# bbwmixer.net
KiCad netlist of a schematic drawn in EAGLE
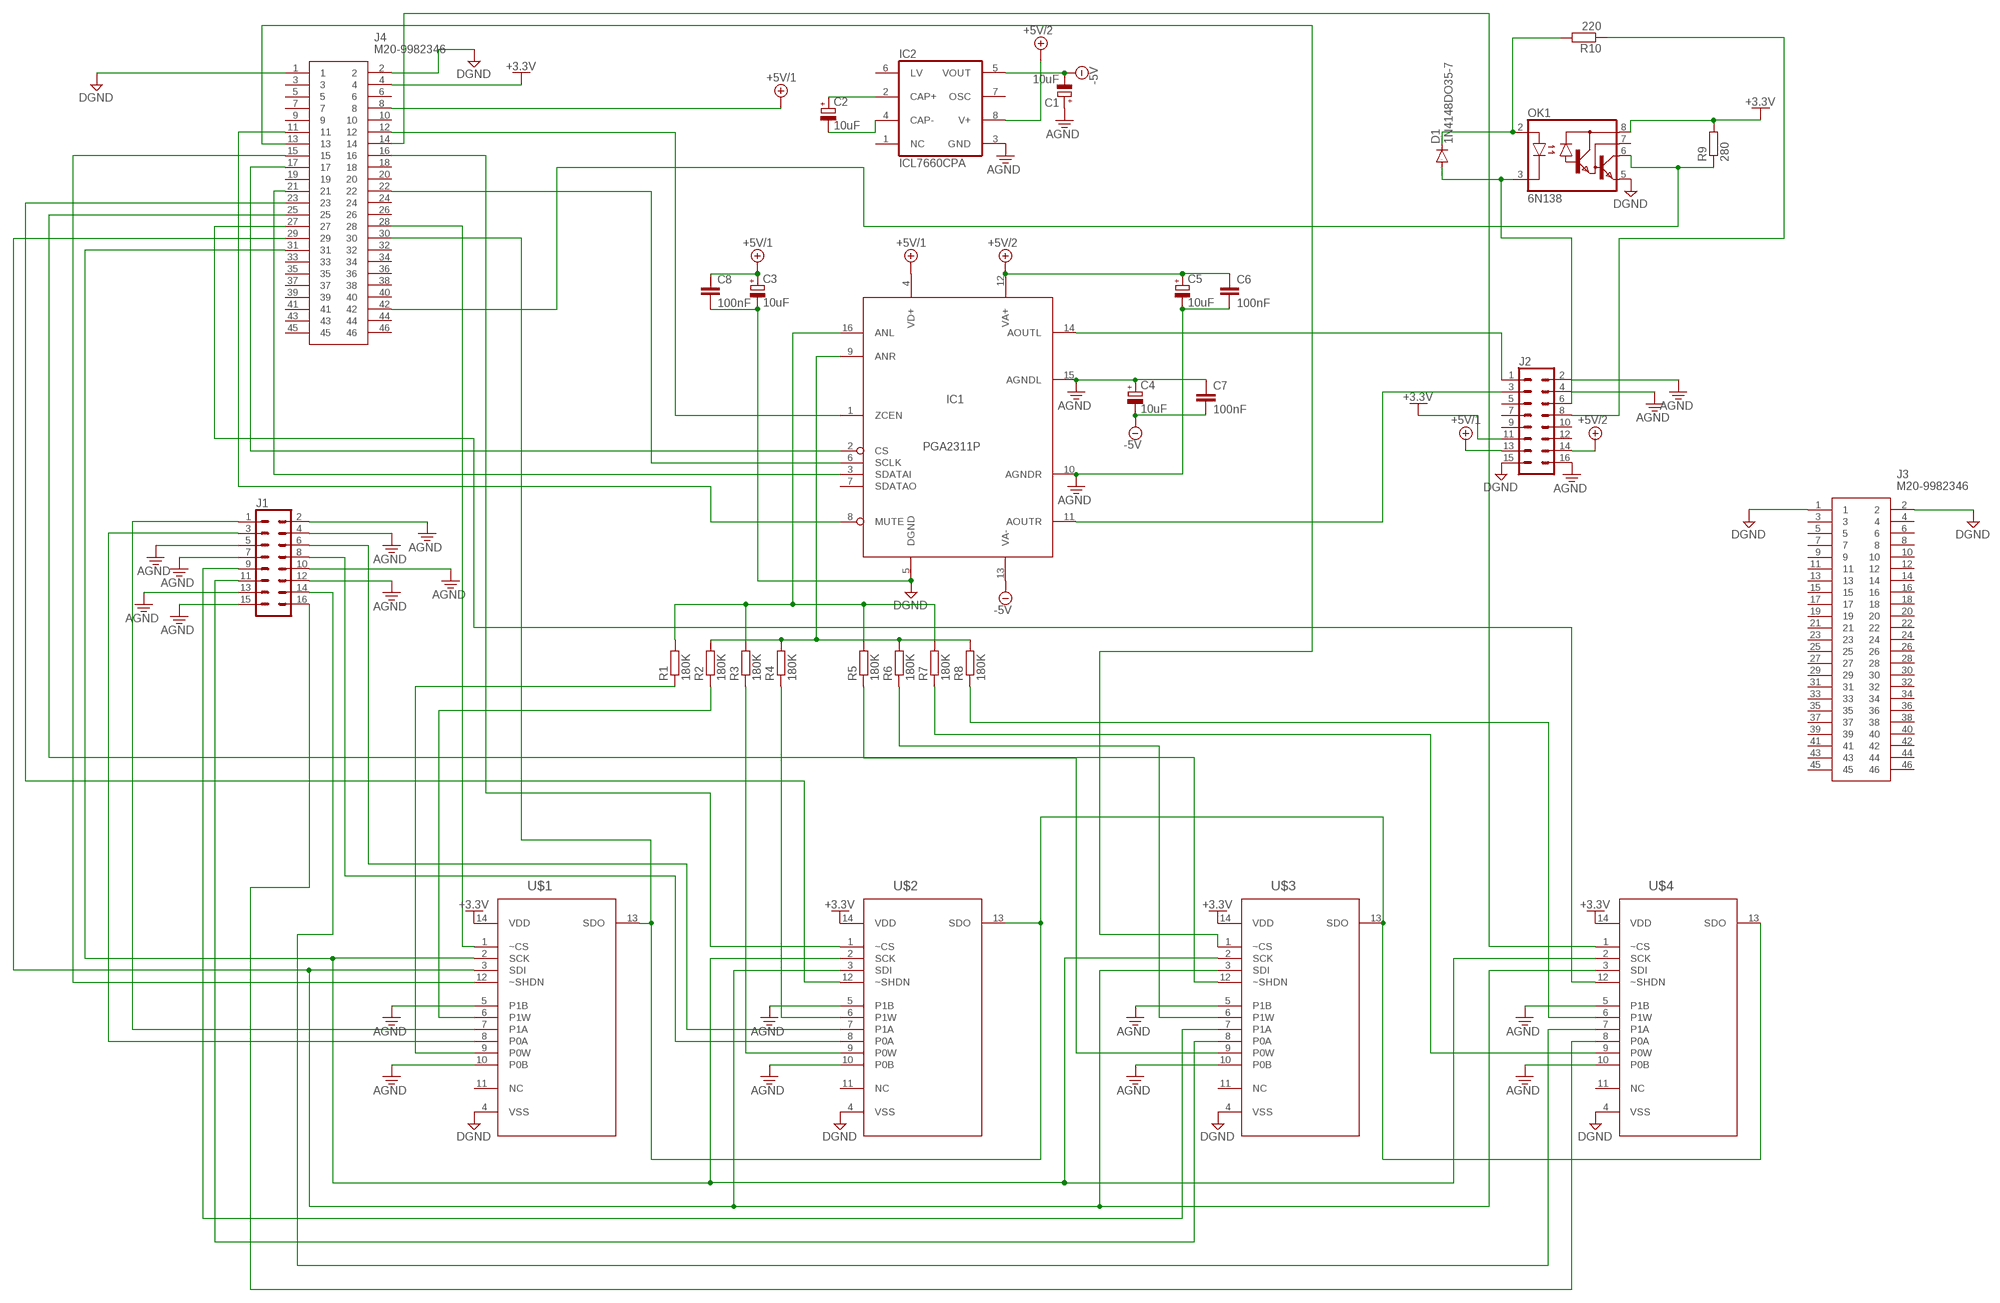
[diagram p0: schematic, sheet 1]

(export (version "E")
  (design (tool "Eeschema 10.0.6"))
  (components
    (comp (ref "C1")
      (value "10uF")
      (footprint "eagle-import:E15-5")
      (libsource (lib "eagle-import") (part "CPOL-EUE15-5AXIAL"))
    )
    (comp (ref "C2")
      (value "10uF")
      (footprint "eagle-import:E15-5")
      (libsource (lib "eagle-import") (part "CPOL-EUE15-5AXIAL"))
    )
    (comp (ref "C3")
      (value "10uF")
      (footprint "eagle-import:E15-5")
      (libsource (lib "eagle-import") (part "CPOL-EUE15-5AXIAL"))
    )
    (comp (ref "C4")
      (value "10uF")
      (footprint "eagle-import:E15-5")
      (libsource (lib "eagle-import") (part "CPOL-EUE15-5AXIAL"))
    )
    (comp (ref "C5")
      (value "10uF")
      (footprint "eagle-import:E15-5")
      (libsource (lib "eagle-import") (part "CPOL-EUE15-5AXIAL"))
    )
    (comp (ref "C6")
      (value "100nF")
      (footprint "eagle-import:C050-025X075")
      (libsource (lib "eagle-import") (part "C-EU050-025X075"))
    )
    (comp (ref "C7")
      (value "100nF")
      (footprint "eagle-import:C050-025X075")
      (libsource (lib "eagle-import") (part "C-EU050-025X075"))
    )
    (comp (ref "C8")
      (value "100nF")
      (footprint "eagle-import:C050-025X075")
      (libsource (lib "eagle-import") (part "C-EU050-025X075"))
    )
    (comp (ref "D1")
      (value "1N4148DO35-7")
      (footprint "eagle-import:DO35-7")
      (libsource (lib "eagle-import") (part "1N4148DO35-7"))
    )
    (comp (ref "IC1")
      (value "PGA2311P")
      (footprint "eagle-import:DIL16")
      (libsource (lib "eagle-import") (part "PGA2311P"))
    )
    (comp (ref "IC2")
      (value "ICL7660CPA")
      (footprint "eagle-import:DIL08")
      (fields (field (name "MF") "INTERSIL"))
      (libsource (lib "eagle-import") (part "ICL7660CPA"))
    )
    (comp (ref "J1")
      (value "CONN_08X2")
      (footprint "eagle-import:2X8")
      (libsource (lib "eagle-import") (part "CONN_08X2"))
    )
    (comp (ref "J2")
      (value "CONN_08X2")
      (footprint "eagle-import:2X8")
      (libsource (lib "eagle-import") (part "CONN_08X2"))
    )
    (comp (ref "J3")
      (value "M20-9982346")
      (footprint "eagle-import:M20-9982346")
      (fields (field (name "MOUSER_PART_NUMBER") "855-M20-9982346"))
      (libsource (lib "eagle-import") (part "M20-9982346"))
    )
    (comp (ref "J4")
      (value "M20-9982346")
      (footprint "eagle-import:M20-9982346")
      (fields (field (name "MOUSER_PART_NUMBER") "855-M20-9982346"))
      (libsource (lib "eagle-import") (part "M20-9982346"))
    )
    (comp (ref "OK1")
      (value "6N138")
      (footprint "eagle-import:DIL08")
      (fields (field (name "MF") "VISHAY/TELEFUNKEN"))
      (libsource (lib "eagle-import") (part "6N138"))
    )
    (comp (ref "R1")
      (value "180K")
      (footprint "eagle-import:0207_10")
      (libsource (lib "eagle-import") (part "R-EU_0207/10"))
    )
    (comp (ref "R2")
      (value "180K")
      (footprint "eagle-import:0207_10")
      (libsource (lib "eagle-import") (part "R-EU_0207/10"))
    )
    (comp (ref "R3")
      (value "180K")
      (footprint "eagle-import:0207_10")
      (libsource (lib "eagle-import") (part "R-EU_0207/10"))
    )
    (comp (ref "R4")
      (value "180K")
      (footprint "eagle-import:0207_10")
      (libsource (lib "eagle-import") (part "R-EU_0207/10"))
    )
    (comp (ref "R5")
      (value "180K")
      (footprint "eagle-import:0207_10")
      (libsource (lib "eagle-import") (part "R-EU_0207/10"))
    )
    (comp (ref "R6")
      (value "180K")
      (footprint "eagle-import:0207_10")
      (libsource (lib "eagle-import") (part "R-EU_0207/10"))
    )
    (comp (ref "R7")
      (value "180K")
      (footprint "eagle-import:0207_10")
      (libsource (lib "eagle-import") (part "R-EU_0207/10"))
    )
    (comp (ref "R8")
      (value "180K")
      (footprint "eagle-import:0207_10")
      (libsource (lib "eagle-import") (part "R-EU_0207/10"))
    )
    (comp (ref "R9")
      (value "280")
      (footprint "eagle-import:0207_10")
      (libsource (lib "eagle-import") (part "R-EU_0207/10"))
    )
    (comp (ref "R10")
      (value "220")
      (footprint "eagle-import:0207_10")
      (libsource (lib "eagle-import") (part "R-EU_0207/10"))
    )
    (comp (ref "U$1")
      (value "MCP4251-103E/P")
      (footprint "eagle-import:DIP254P762X533-14")
      (fields (field (name "MF") "Microchip Technology / Atmel"))
      (libsource (lib "eagle-import") (part "MCP4251-103E/P"))
    )
    (comp (ref "U$2")
      (value "MCP4251-103E/P")
      (footprint "eagle-import:DIP254P762X533-14")
      (fields (field (name "MF") "Microchip Technology / Atmel"))
      (libsource (lib "eagle-import") (part "MCP4251-103E/P"))
    )
    (comp (ref "U$3")
      (value "MCP4251-103E/P")
      (footprint "eagle-import:DIP254P762X533-14")
      (fields (field (name "MF") "Microchip Technology / Atmel"))
      (libsource (lib "eagle-import") (part "MCP4251-103E/P"))
    )
    (comp (ref "U$4")
      (value "MCP4251-103E/P")
      (footprint "eagle-import:DIP254P762X533-14")
      (fields (field (name "MF") "Microchip Technology / Atmel"))
      (libsource (lib "eagle-import") (part "MCP4251-103E/P"))
    )
  )
  (nets
    (net (code "1") (name "+3.3V") (class "Default")
      (node (ref "J2") (pin "11") (pinfunction "11_11") (pintype "passive"))
      (node (ref "J4") (pin "4") (pinfunction "4_4") (pintype "bidirectional"))
      (node (ref "OK1") (pin "8") (pinfunction "VCC_8") (pintype "passive"))
      (node (ref "R9") (pin "2") (pinfunction "2_2") (pintype "passive"))
      (node (ref "U$1") (pin "14") (pinfunction "VDD_14") (pintype "power_in"))
      (node (ref "U$2") (pin "14") (pinfunction "VDD_14") (pintype "power_in"))
      (node (ref "U$3") (pin "14") (pinfunction "VDD_14") (pintype "power_in"))
      (node (ref "U$4") (pin "14") (pinfunction "VDD_14") (pintype "power_in"))
    )
    (net (code "2") (name "+5V{slash}1") (class "Default")
      (node (ref "C3") (pin "+") (pinfunction "+_+") (pintype "passive"))
      (node (ref "C8") (pin "1") (pinfunction "1_1") (pintype "passive"))
      (node (ref "IC1") (pin "4") (pinfunction "VD+_4") (pintype "power_in"))
      (node (ref "J2") (pin "13") (pinfunction "13_13") (pintype "passive"))
      (node (ref "J4") (pin "8") (pinfunction "8_8") (pintype "bidirectional"))
    )
    (net (code "3") (name "+5V{slash}2") (class "Default")
      (node (ref "IC1") (pin "12") (pinfunction "VA+_12") (pintype "power_in"))
      (node (ref "IC2") (pin "8") (pinfunction "V+_8") (pintype "power_in"))
      (node (ref "J2") (pin "14") (pinfunction "14_14") (pintype "passive"))
    )
    (net (code "4") (name "-5V") (class "Default")
      (node (ref "C1") (pin "-") (pinfunction "-_-") (pintype "passive"))
      (node (ref "C4") (pin "-") (pinfunction "-_-") (pintype "passive"))
      (node (ref "C7") (pin "2") (pinfunction "2_2") (pintype "passive"))
      (node (ref "IC1") (pin "13") (pinfunction "VA-_13") (pintype "power_in"))
      (node (ref "IC2") (pin "5") (pinfunction "VOUT_5") (pintype "output"))
    )
    (net (code "5") (name "AGND") (class "Default")
      (node (ref "C1") (pin "+") (pinfunction "+_+") (pintype "passive"))
      (node (ref "C4") (pin "+") (pinfunction "+_+") (pintype "passive"))
      (node (ref "C5") (pin "-") (pinfunction "-_-") (pintype "passive"))
      (node (ref "C6") (pin "2") (pinfunction "2_2") (pintype "passive"))
      (node (ref "C7") (pin "1") (pinfunction "1_1") (pintype "passive"))
      (node (ref "IC1") (pin "10") (pinfunction "AGNDR_10") (pintype "power_in"))
      (node (ref "IC1") (pin "15") (pinfunction "AGNDL_15") (pintype "power_in"))
      (node (ref "IC2") (pin "3") (pinfunction "GND_3") (pintype "power_in"))
      (node (ref "J1") (pin "10") (pinfunction "10_10") (pintype "passive"))
      (node (ref "J1") (pin "12") (pinfunction "12_12") (pintype "passive"))
      (node (ref "J1") (pin "13") (pinfunction "13_13") (pintype "passive"))
      (node (ref "J1") (pin "15") (pinfunction "15_15") (pintype "passive"))
      (node (ref "J1") (pin "2") (pinfunction "2_2") (pintype "passive"))
      (node (ref "J1") (pin "4") (pinfunction "4_4") (pintype "passive"))
      (node (ref "J1") (pin "5") (pinfunction "5_5") (pintype "passive"))
      (node (ref "J1") (pin "7") (pinfunction "7_7") (pintype "passive"))
      (node (ref "J2") (pin "16") (pinfunction "16_16") (pintype "passive"))
      (node (ref "J2") (pin "2") (pinfunction "2_2") (pintype "passive"))
      (node (ref "J2") (pin "4") (pinfunction "4_4") (pintype "passive"))
      (node (ref "U$1") (pin "10") (pinfunction "P0B_10") (pintype "passive"))
      (node (ref "U$1") (pin "5") (pinfunction "P1B_5") (pintype "passive"))
      (node (ref "U$2") (pin "10") (pinfunction "P0B_10") (pintype "passive"))
      (node (ref "U$2") (pin "5") (pinfunction "P1B_5") (pintype "passive"))
      (node (ref "U$3") (pin "10") (pinfunction "P0B_10") (pintype "passive"))
      (node (ref "U$3") (pin "5") (pinfunction "P1B_5") (pintype "passive"))
      (node (ref "U$4") (pin "10") (pinfunction "P0B_10") (pintype "passive"))
      (node (ref "U$4") (pin "5") (pinfunction "P1B_5") (pintype "passive"))
    )
    (net (code "6") (name "DGND") (class "Default")
      (node (ref "C3") (pin "-") (pinfunction "-_-") (pintype "passive"))
      (node (ref "C8") (pin "2") (pinfunction "2_2") (pintype "passive"))
      (node (ref "IC1") (pin "5") (pinfunction "DGND_5") (pintype "power_in"))
      (node (ref "J2") (pin "15") (pinfunction "15_15") (pintype "passive"))
      (node (ref "J3") (pin "1") (pinfunction "1_1") (pintype "bidirectional"))
      (node (ref "J3") (pin "2") (pinfunction "2_2") (pintype "bidirectional"))
      (node (ref "J4") (pin "1") (pinfunction "1_1") (pintype "bidirectional"))
      (node (ref "J4") (pin "2") (pinfunction "2_2") (pintype "bidirectional"))
      (node (ref "OK1") (pin "5") (pinfunction "GND_5") (pintype "passive"))
      (node (ref "U$1") (pin "4") (pinfunction "VSS_4") (pintype "passive"))
      (node (ref "U$2") (pin "4") (pinfunction "VSS_4") (pintype "passive"))
      (node (ref "U$3") (pin "4") (pinfunction "VSS_4") (pintype "passive"))
      (node (ref "U$4") (pin "4") (pinfunction "VSS_4") (pintype "passive"))
    )
    (net (code "7") (name "Net-(C5-Pad+)") (class "Default")
      (node (ref "C5") (pin "+") (pinfunction "+_+") (pintype "passive"))
      (node (ref "C6") (pin "1") (pinfunction "1_1") (pintype "passive"))
    )
    (net (code "8") (name "Net-(IC1-ANL)") (class "Default")
      (node (ref "IC1") (pin "16") (pinfunction "ANL_16") (pintype "input"))
      (node (ref "R1") (pin "2") (pinfunction "2_2") (pintype "passive"))
      (node (ref "R3") (pin "2") (pinfunction "2_2") (pintype "passive"))
      (node (ref "R5") (pin "2") (pinfunction "2_2") (pintype "passive"))
      (node (ref "R7") (pin "2") (pinfunction "2_2") (pintype "passive"))
    )
    (net (code "9") (name "Net-(IC1-ANR)") (class "Default")
      (node (ref "IC1") (pin "9") (pinfunction "ANR_9") (pintype "input"))
      (node (ref "R2") (pin "2") (pinfunction "2_2") (pintype "passive"))
      (node (ref "R4") (pin "2") (pinfunction "2_2") (pintype "passive"))
      (node (ref "R6") (pin "2") (pinfunction "2_2") (pintype "passive"))
      (node (ref "R8") (pin "2") (pinfunction "2_2") (pintype "passive"))
    )
    (net (code "10") (name "Net-(IC1-AOUTL)") (class "Default")
      (node (ref "IC1") (pin "14") (pinfunction "AOUTL_14") (pintype "output"))
      (node (ref "J2") (pin "1") (pinfunction "1_1") (pintype "passive"))
    )
    (net (code "11") (name "Net-(IC1-AOUTR)") (class "Default")
      (node (ref "IC1") (pin "11") (pinfunction "AOUTR_11") (pintype "output"))
      (node (ref "J2") (pin "3") (pinfunction "3_3") (pintype "passive"))
    )
    (net (code "12") (name "Net-(IC1-CS)") (class "Default")
      (node (ref "IC1") (pin "2") (pinfunction "CS_2") (pintype "input"))
      (node (ref "J4") (pin "17") (pinfunction "17_17") (pintype "bidirectional"))
    )
    (net (code "13") (name "Net-(IC1-MUTE)") (class "Default")
      (node (ref "IC1") (pin "8") (pinfunction "MUTE_8") (pintype "input"))
      (node (ref "J4") (pin "11") (pinfunction "11_11") (pintype "bidirectional"))
    )
    (net (code "14") (name "Net-(IC1-SCLK)") (class "Default")
      (node (ref "IC1") (pin "6") (pinfunction "SCLK_6") (pintype "input"))
      (node (ref "J4") (pin "22") (pinfunction "22_22") (pintype "bidirectional"))
    )
    (net (code "15") (name "Net-(IC1-SDATAI)") (class "Default")
      (node (ref "IC1") (pin "3") (pinfunction "SDATAI_3") (pintype "input"))
      (node (ref "J4") (pin "21") (pinfunction "21_21") (pintype "bidirectional"))
    )
    (net (code "16") (name "Net-(IC1-ZCEN)") (class "Default")
      (node (ref "IC1") (pin "1") (pinfunction "ZCEN_1") (pintype "input"))
      (node (ref "J4") (pin "12") (pinfunction "12_12") (pintype "bidirectional"))
    )
    (net (code "17") (name "Net-(IC2-CAP+)") (class "Default")
      (node (ref "C2") (pin "+") (pinfunction "+_+") (pintype "passive"))
      (node (ref "IC2") (pin "2") (pinfunction "CAP+_2") (pintype "passive"))
    )
    (net (code "18") (name "Net-(IC2-CAP-)") (class "Default")
      (node (ref "C2") (pin "-") (pinfunction "-_-") (pintype "passive"))
      (node (ref "IC2") (pin "4") (pinfunction "CAP-_4") (pintype "passive"))
    )
    (net (code "19") (name "Net-(J2-Pad8)") (class "Default")
      (node (ref "J2") (pin "8") (pinfunction "8_8") (pintype "passive"))
      (node (ref "R10") (pin "1") (pinfunction "1_1") (pintype "passive"))
    )
    (net (code "20") (name "Net-(OK1-A)") (class "Default")
      (node (ref "D1") (pin "C") (pinfunction "C_C") (pintype "passive"))
      (node (ref "OK1") (pin "2") (pinfunction "A_2") (pintype "passive"))
      (node (ref "R10") (pin "2") (pinfunction "2_2") (pintype "passive"))
    )
    (net (code "21") (name "Net-(OK1-C)") (class "Default")
      (node (ref "D1") (pin "A") (pinfunction "A_A") (pintype "passive"))
      (node (ref "J2") (pin "6") (pinfunction "6_6") (pintype "passive"))
      (node (ref "OK1") (pin "3") (pinfunction "C_3") (pintype "passive"))
    )
    (net (code "22") (name "Net-(OK1-VO)") (class "Default")
      (node (ref "J4") (pin "42") (pinfunction "42_42") (pintype "bidirectional"))
      (node (ref "OK1") (pin "6") (pinfunction "VO_6") (pintype "passive"))
      (node (ref "R9") (pin "1") (pinfunction "1_1") (pintype "passive"))
    )
    (net (code "23") (name "Net-(U$1-P0A)") (class "Default")
      (node (ref "J1") (pin "3") (pinfunction "3_3") (pintype "passive"))
      (node (ref "U$1") (pin "8") (pinfunction "P0A_8") (pintype "passive"))
    )
    (net (code "24") (name "Net-(U$1-P0W)") (class "Default")
      (node (ref "R1") (pin "1") (pinfunction "1_1") (pintype "passive"))
      (node (ref "U$1") (pin "9") (pinfunction "P0W_9") (pintype "passive"))
    )
    (net (code "25") (name "Net-(U$1-P1A)") (class "Default")
      (node (ref "J1") (pin "1") (pinfunction "1_1") (pintype "passive"))
      (node (ref "U$1") (pin "7") (pinfunction "P1A_7") (pintype "passive"))
    )
    (net (code "26") (name "Net-(U$1-P1W)") (class "Default")
      (node (ref "R2") (pin "1") (pinfunction "1_1") (pintype "passive"))
      (node (ref "U$1") (pin "6") (pinfunction "P1W_6") (pintype "passive"))
    )
    (net (code "27") (name "Net-(U$1-SCK)") (class "Default")
      (node (ref "J4") (pin "31") (pinfunction "31_31") (pintype "bidirectional"))
      (node (ref "U$1") (pin "2") (pinfunction "SCK_2") (pintype "input"))
      (node (ref "U$2") (pin "2") (pinfunction "SCK_2") (pintype "input"))
      (node (ref "U$3") (pin "2") (pinfunction "SCK_2") (pintype "input"))
      (node (ref "U$4") (pin "2") (pinfunction "SCK_2") (pintype "input"))
    )
    (net (code "28") (name "Net-(U$1-SDI)") (class "Default")
      (node (ref "J4") (pin "29") (pinfunction "29_29") (pintype "bidirectional"))
      (node (ref "U$1") (pin "3") (pinfunction "SDI_3") (pintype "input"))
      (node (ref "U$2") (pin "3") (pinfunction "SDI_3") (pintype "input"))
      (node (ref "U$3") (pin "3") (pinfunction "SDI_3") (pintype "input"))
      (node (ref "U$4") (pin "3") (pinfunction "SDI_3") (pintype "input"))
    )
    (net (code "29") (name "Net-(U$1-SDO)") (class "Default")
      (node (ref "J4") (pin "30") (pinfunction "30_30") (pintype "bidirectional"))
      (node (ref "U$1") (pin "13") (pinfunction "SDO_13") (pintype "output"))
      (node (ref "U$2") (pin "13") (pinfunction "SDO_13") (pintype "output"))
      (node (ref "U$3") (pin "13") (pinfunction "SDO_13") (pintype "output"))
      (node (ref "U$4") (pin "13") (pinfunction "SDO_13") (pintype "output"))
    )
    (net (code "30") (name "Net-(U$1-~{CS})") (class "Default")
      (node (ref "J4") (pin "28") (pinfunction "28_28") (pintype "bidirectional"))
      (node (ref "U$1") (pin "1") (pinfunction "~{CS}_1") (pintype "input"))
    )
    (net (code "31") (name "Net-(U$1-~{SHDN})") (class "Default")
      (node (ref "J4") (pin "15") (pinfunction "15_15") (pintype "bidirectional"))
      (node (ref "U$1") (pin "12") (pinfunction "~{SHDN}_12") (pintype "input"))
    )
    (net (code "32") (name "Net-(U$2-P0A)") (class "Default")
      (node (ref "J1") (pin "8") (pinfunction "8_8") (pintype "passive"))
      (node (ref "U$2") (pin "8") (pinfunction "P0A_8") (pintype "passive"))
    )
    (net (code "33") (name "Net-(U$2-P0W)") (class "Default")
      (node (ref "R3") (pin "1") (pinfunction "1_1") (pintype "passive"))
      (node (ref "U$2") (pin "9") (pinfunction "P0W_9") (pintype "passive"))
    )
    (net (code "34") (name "Net-(U$2-P1A)") (class "Default")
      (node (ref "J1") (pin "6") (pinfunction "6_6") (pintype "passive"))
      (node (ref "U$2") (pin "7") (pinfunction "P1A_7") (pintype "passive"))
    )
    (net (code "35") (name "Net-(U$2-P1W)") (class "Default")
      (node (ref "R4") (pin "1") (pinfunction "1_1") (pintype "passive"))
      (node (ref "U$2") (pin "6") (pinfunction "P1W_6") (pintype "passive"))
    )
    (net (code "36") (name "Net-(U$2-~{CS})") (class "Default")
      (node (ref "J4") (pin "16") (pinfunction "16_16") (pintype "bidirectional"))
      (node (ref "U$2") (pin "1") (pinfunction "~{CS}_1") (pintype "input"))
    )
    (net (code "37") (name "Net-(U$2-~{SHDN})") (class "Default")
      (node (ref "J4") (pin "23") (pinfunction "23_23") (pintype "bidirectional"))
      (node (ref "U$2") (pin "12") (pinfunction "~{SHDN}_12") (pintype "input"))
    )
    (net (code "38") (name "Net-(U$3-P0A)") (class "Default")
      (node (ref "J1") (pin "11") (pinfunction "11_11") (pintype "passive"))
      (node (ref "U$3") (pin "8") (pinfunction "P0A_8") (pintype "passive"))
    )
    (net (code "39") (name "Net-(U$3-P0W)") (class "Default")
      (node (ref "R5") (pin "1") (pinfunction "1_1") (pintype "passive"))
      (node (ref "U$3") (pin "9") (pinfunction "P0W_9") (pintype "passive"))
    )
    (net (code "40") (name "Net-(U$3-P1A)") (class "Default")
      (node (ref "J1") (pin "9") (pinfunction "9_9") (pintype "passive"))
      (node (ref "U$3") (pin "7") (pinfunction "P1A_7") (pintype "passive"))
    )
    (net (code "41") (name "Net-(U$3-P1W)") (class "Default")
      (node (ref "R6") (pin "1") (pinfunction "1_1") (pintype "passive"))
      (node (ref "U$3") (pin "6") (pinfunction "P1W_6") (pintype "passive"))
    )
    (net (code "42") (name "Net-(U$3-~{CS})") (class "Default")
      (node (ref "J4") (pin "13") (pinfunction "13_13") (pintype "bidirectional"))
      (node (ref "U$3") (pin "1") (pinfunction "~{CS}_1") (pintype "input"))
    )
    (net (code "43") (name "Net-(U$3-~{SHDN})") (class "Default")
      (node (ref "J4") (pin "25") (pinfunction "25_25") (pintype "bidirectional"))
      (node (ref "U$3") (pin "12") (pinfunction "~{SHDN}_12") (pintype "input"))
    )
    (net (code "44") (name "Net-(U$4-P0A)") (class "Default")
      (node (ref "J1") (pin "16") (pinfunction "16_16") (pintype "passive"))
      (node (ref "U$4") (pin "8") (pinfunction "P0A_8") (pintype "passive"))
    )
    (net (code "45") (name "Net-(U$4-P0W)") (class "Default")
      (node (ref "R7") (pin "1") (pinfunction "1_1") (pintype "passive"))
      (node (ref "U$4") (pin "9") (pinfunction "P0W_9") (pintype "passive"))
    )
    (net (code "46") (name "Net-(U$4-P1A)") (class "Default")
      (node (ref "J1") (pin "14") (pinfunction "14_14") (pintype "passive"))
      (node (ref "U$4") (pin "7") (pinfunction "P1A_7") (pintype "passive"))
    )
    (net (code "47") (name "Net-(U$4-P1W)") (class "Default")
      (node (ref "R8") (pin "1") (pinfunction "1_1") (pintype "passive"))
      (node (ref "U$4") (pin "6") (pinfunction "P1W_6") (pintype "passive"))
    )
    (net (code "48") (name "Net-(U$4-~{CS})") (class "Default")
      (node (ref "J4") (pin "14") (pinfunction "14_14") (pintype "bidirectional"))
      (node (ref "U$4") (pin "1") (pinfunction "~{CS}_1") (pintype "input"))
    )
    (net (code "49") (name "Net-(U$4-~{SHDN})") (class "Default")
      (node (ref "J4") (pin "27") (pinfunction "27_27") (pintype "bidirectional"))
      (node (ref "U$4") (pin "12") (pinfunction "~{SHDN}_12") (pintype "input"))
    )
    (net (code "50") (name "unconnected-(IC1-SDATAO-Pad7)") (class "Default")
      (node (ref "IC1") (pin "7") (pinfunction "SDATAO_7") (pintype "output"))
    )
    (net (code "51") (name "unconnected-(IC2-LV-Pad6)") (class "Default")
      (node (ref "IC2") (pin "6") (pinfunction "LV_6") (pintype "passive"))
    )
    (net (code "52") (name "unconnected-(IC2-NC-Pad1)") (class "Default")
      (node (ref "IC2") (pin "1") (pinfunction "NC_1") (pintype "no_connect"))
    )
    (net (code "53") (name "unconnected-(IC2-OSC-Pad7)") (class "Default")
      (node (ref "IC2") (pin "7") (pinfunction "OSC_7") (pintype "output"))
    )
    (net (code "54") (name "unconnected-(J2-Pad5)") (class "Default")
      (node (ref "J2") (pin "5") (pinfunction "5_5") (pintype "passive"))
    )
    (net (code "55") (name "unconnected-(J2-Pad7)") (class "Default")
      (node (ref "J2") (pin "7") (pinfunction "7_7") (pintype "passive"))
    )
    (net (code "56") (name "unconnected-(J2-Pad9)") (class "Default")
      (node (ref "J2") (pin "9") (pinfunction "9_9") (pintype "passive"))
    )
    (net (code "57") (name "unconnected-(J2-Pad10)") (class "Default")
      (node (ref "J2") (pin "10") (pinfunction "10_10") (pintype "passive"))
    )
    (net (code "58") (name "unconnected-(J2-Pad12)") (class "Default")
      (node (ref "J2") (pin "12") (pinfunction "12_12") (pintype "passive"))
    )
    (net (code "59") (name "unconnected-(J3-Pad3)") (class "Default")
      (node (ref "J3") (pin "3") (pinfunction "3_3") (pintype "bidirectional"))
    )
    (net (code "60") (name "unconnected-(J3-Pad4)") (class "Default")
      (node (ref "J3") (pin "4") (pinfunction "4_4") (pintype "bidirectional"))
    )
    (net (code "61") (name "unconnected-(J3-Pad5)") (class "Default")
      (node (ref "J3") (pin "5") (pinfunction "5_5") (pintype "bidirectional"))
    )
    (net (code "62") (name "unconnected-(J3-Pad6)") (class "Default")
      (node (ref "J3") (pin "6") (pinfunction "6_6") (pintype "bidirectional"))
    )
    (net (code "63") (name "unconnected-(J3-Pad7)") (class "Default")
      (node (ref "J3") (pin "7") (pinfunction "7_7") (pintype "bidirectional"))
    )
    (net (code "64") (name "unconnected-(J3-Pad8)") (class "Default")
      (node (ref "J3") (pin "8") (pinfunction "8_8") (pintype "bidirectional"))
    )
    (net (code "65") (name "unconnected-(J3-Pad9)") (class "Default")
      (node (ref "J3") (pin "9") (pinfunction "9_9") (pintype "bidirectional"))
    )
    (net (code "66") (name "unconnected-(J3-Pad10)") (class "Default")
      (node (ref "J3") (pin "10") (pinfunction "10_10") (pintype "bidirectional"))
    )
    (net (code "67") (name "unconnected-(J3-Pad11)") (class "Default")
      (node (ref "J3") (pin "11") (pinfunction "11_11") (pintype "bidirectional"))
    )
    (net (code "68") (name "unconnected-(J3-Pad12)") (class "Default")
      (node (ref "J3") (pin "12") (pinfunction "12_12") (pintype "bidirectional"))
    )
    (net (code "69") (name "unconnected-(J3-Pad13)") (class "Default")
      (node (ref "J3") (pin "13") (pinfunction "13_13") (pintype "bidirectional"))
    )
    (net (code "70") (name "unconnected-(J3-Pad14)") (class "Default")
      (node (ref "J3") (pin "14") (pinfunction "14_14") (pintype "bidirectional"))
    )
    (net (code "71") (name "unconnected-(J3-Pad15)") (class "Default")
      (node (ref "J3") (pin "15") (pinfunction "15_15") (pintype "bidirectional"))
    )
    (net (code "72") (name "unconnected-(J3-Pad16)") (class "Default")
      (node (ref "J3") (pin "16") (pinfunction "16_16") (pintype "bidirectional"))
    )
    (net (code "73") (name "unconnected-(J3-Pad17)") (class "Default")
      (node (ref "J3") (pin "17") (pinfunction "17_17") (pintype "bidirectional"))
    )
    (net (code "74") (name "unconnected-(J3-Pad18)") (class "Default")
      (node (ref "J3") (pin "18") (pinfunction "18_18") (pintype "bidirectional"))
    )
    (net (code "75") (name "unconnected-(J3-Pad19)") (class "Default")
      (node (ref "J3") (pin "19") (pinfunction "19_19") (pintype "bidirectional"))
    )
    (net (code "76") (name "unconnected-(J3-Pad20)") (class "Default")
      (node (ref "J3") (pin "20") (pinfunction "20_20") (pintype "bidirectional"))
    )
    (net (code "77") (name "unconnected-(J3-Pad21)") (class "Default")
      (node (ref "J3") (pin "21") (pinfunction "21_21") (pintype "bidirectional"))
    )
    (net (code "78") (name "unconnected-(J3-Pad22)") (class "Default")
      (node (ref "J3") (pin "22") (pinfunction "22_22") (pintype "bidirectional"))
    )
    (net (code "79") (name "unconnected-(J3-Pad23)") (class "Default")
      (node (ref "J3") (pin "23") (pinfunction "23_23") (pintype "bidirectional"))
    )
    (net (code "80") (name "unconnected-(J3-Pad24)") (class "Default")
      (node (ref "J3") (pin "24") (pinfunction "24_24") (pintype "bidirectional"))
    )
    (net (code "81") (name "unconnected-(J3-Pad25)") (class "Default")
      (node (ref "J3") (pin "25") (pinfunction "25_25") (pintype "bidirectional"))
    )
    (net (code "82") (name "unconnected-(J3-Pad26)") (class "Default")
      (node (ref "J3") (pin "26") (pinfunction "26_26") (pintype "bidirectional"))
    )
    (net (code "83") (name "unconnected-(J3-Pad27)") (class "Default")
      (node (ref "J3") (pin "27") (pinfunction "27_27") (pintype "bidirectional"))
    )
    (net (code "84") (name "unconnected-(J3-Pad28)") (class "Default")
      (node (ref "J3") (pin "28") (pinfunction "28_28") (pintype "bidirectional"))
    )
    (net (code "85") (name "unconnected-(J3-Pad29)") (class "Default")
      (node (ref "J3") (pin "29") (pinfunction "29_29") (pintype "bidirectional"))
    )
    (net (code "86") (name "unconnected-(J3-Pad30)") (class "Default")
      (node (ref "J3") (pin "30") (pinfunction "30_30") (pintype "bidirectional"))
    )
    (net (code "87") (name "unconnected-(J3-Pad31)") (class "Default")
      (node (ref "J3") (pin "31") (pinfunction "31_31") (pintype "bidirectional"))
    )
    (net (code "88") (name "unconnected-(J3-Pad32)") (class "Default")
      (node (ref "J3") (pin "32") (pinfunction "32_32") (pintype "bidirectional"))
    )
    (net (code "89") (name "unconnected-(J3-Pad33)") (class "Default")
      (node (ref "J3") (pin "33") (pinfunction "33_33") (pintype "bidirectional"))
    )
    (net (code "90") (name "unconnected-(J3-Pad34)") (class "Default")
      (node (ref "J3") (pin "34") (pinfunction "34_34") (pintype "bidirectional"))
    )
    (net (code "91") (name "unconnected-(J3-Pad35)") (class "Default")
      (node (ref "J3") (pin "35") (pinfunction "35_35") (pintype "bidirectional"))
    )
    (net (code "92") (name "unconnected-(J3-Pad36)") (class "Default")
      (node (ref "J3") (pin "36") (pinfunction "36_36") (pintype "bidirectional"))
    )
    (net (code "93") (name "unconnected-(J3-Pad37)") (class "Default")
      (node (ref "J3") (pin "37") (pinfunction "37_37") (pintype "bidirectional"))
    )
    (net (code "94") (name "unconnected-(J3-Pad38)") (class "Default")
      (node (ref "J3") (pin "38") (pinfunction "38_38") (pintype "bidirectional"))
    )
    (net (code "95") (name "unconnected-(J3-Pad39)") (class "Default")
      (node (ref "J3") (pin "39") (pinfunction "39_39") (pintype "bidirectional"))
    )
    (net (code "96") (name "unconnected-(J3-Pad40)") (class "Default")
      (node (ref "J3") (pin "40") (pinfunction "40_40") (pintype "bidirectional"))
    )
    (net (code "97") (name "unconnected-(J3-Pad41)") (class "Default")
      (node (ref "J3") (pin "41") (pinfunction "41_41") (pintype "bidirectional"))
    )
    (net (code "98") (name "unconnected-(J3-Pad42)") (class "Default")
      (node (ref "J3") (pin "42") (pinfunction "42_42") (pintype "bidirectional"))
    )
    (net (code "99") (name "unconnected-(J3-Pad43)") (class "Default")
      (node (ref "J3") (pin "43") (pinfunction "43_43") (pintype "bidirectional"))
    )
    (net (code "100") (name "unconnected-(J3-Pad44)") (class "Default")
      (node (ref "J3") (pin "44") (pinfunction "44_44") (pintype "bidirectional"))
    )
    (net (code "101") (name "unconnected-(J3-Pad45)") (class "Default")
      (node (ref "J3") (pin "45") (pinfunction "45_45") (pintype "bidirectional"))
    )
    (net (code "102") (name "unconnected-(J3-Pad46)") (class "Default")
      (node (ref "J3") (pin "46") (pinfunction "46_46") (pintype "bidirectional"))
    )
    (net (code "103") (name "unconnected-(J4-Pad3)") (class "Default")
      (node (ref "J4") (pin "3") (pinfunction "3_3") (pintype "bidirectional"))
    )
    (net (code "104") (name "unconnected-(J4-Pad5)") (class "Default")
      (node (ref "J4") (pin "5") (pinfunction "5_5") (pintype "bidirectional"))
    )
    (net (code "105") (name "unconnected-(J4-Pad6)") (class "Default")
      (node (ref "J4") (pin "6") (pinfunction "6_6") (pintype "bidirectional"))
    )
    (net (code "106") (name "unconnected-(J4-Pad7)") (class "Default")
      (node (ref "J4") (pin "7") (pinfunction "7_7") (pintype "bidirectional"))
    )
    (net (code "107") (name "unconnected-(J4-Pad9)") (class "Default")
      (node (ref "J4") (pin "9") (pinfunction "9_9") (pintype "bidirectional"))
    )
    (net (code "108") (name "unconnected-(J4-Pad10)") (class "Default")
      (node (ref "J4") (pin "10") (pinfunction "10_10") (pintype "bidirectional"))
    )
    (net (code "109") (name "unconnected-(J4-Pad18)") (class "Default")
      (node (ref "J4") (pin "18") (pinfunction "18_18") (pintype "bidirectional"))
    )
    (net (code "110") (name "unconnected-(J4-Pad19)") (class "Default")
      (node (ref "J4") (pin "19") (pinfunction "19_19") (pintype "bidirectional"))
    )
    (net (code "111") (name "unconnected-(J4-Pad20)") (class "Default")
      (node (ref "J4") (pin "20") (pinfunction "20_20") (pintype "bidirectional"))
    )
    (net (code "112") (name "unconnected-(J4-Pad24)") (class "Default")
      (node (ref "J4") (pin "24") (pinfunction "24_24") (pintype "bidirectional"))
    )
    (net (code "113") (name "unconnected-(J4-Pad26)") (class "Default")
      (node (ref "J4") (pin "26") (pinfunction "26_26") (pintype "bidirectional"))
    )
    (net (code "114") (name "unconnected-(J4-Pad32)") (class "Default")
      (node (ref "J4") (pin "32") (pinfunction "32_32") (pintype "bidirectional"))
    )
    (net (code "115") (name "unconnected-(J4-Pad33)") (class "Default")
      (node (ref "J4") (pin "33") (pinfunction "33_33") (pintype "bidirectional"))
    )
    (net (code "116") (name "unconnected-(J4-Pad34)") (class "Default")
      (node (ref "J4") (pin "34") (pinfunction "34_34") (pintype "bidirectional"))
    )
    (net (code "117") (name "unconnected-(J4-Pad35)") (class "Default")
      (node (ref "J4") (pin "35") (pinfunction "35_35") (pintype "bidirectional"))
    )
    (net (code "118") (name "unconnected-(J4-Pad36)") (class "Default")
      (node (ref "J4") (pin "36") (pinfunction "36_36") (pintype "bidirectional"))
    )
    (net (code "119") (name "unconnected-(J4-Pad37)") (class "Default")
      (node (ref "J4") (pin "37") (pinfunction "37_37") (pintype "bidirectional"))
    )
    (net (code "120") (name "unconnected-(J4-Pad38)") (class "Default")
      (node (ref "J4") (pin "38") (pinfunction "38_38") (pintype "bidirectional"))
    )
    (net (code "121") (name "unconnected-(J4-Pad39)") (class "Default")
      (node (ref "J4") (pin "39") (pinfunction "39_39") (pintype "bidirectional"))
    )
    (net (code "122") (name "unconnected-(J4-Pad40)") (class "Default")
      (node (ref "J4") (pin "40") (pinfunction "40_40") (pintype "bidirectional"))
    )
    (net (code "123") (name "unconnected-(J4-Pad41)") (class "Default")
      (node (ref "J4") (pin "41") (pinfunction "41_41") (pintype "bidirectional"))
    )
    (net (code "124") (name "unconnected-(J4-Pad43)") (class "Default")
      (node (ref "J4") (pin "43") (pinfunction "43_43") (pintype "bidirectional"))
    )
    (net (code "125") (name "unconnected-(J4-Pad44)") (class "Default")
      (node (ref "J4") (pin "44") (pinfunction "44_44") (pintype "bidirectional"))
    )
    (net (code "126") (name "unconnected-(J4-Pad45)") (class "Default")
      (node (ref "J4") (pin "45") (pinfunction "45_45") (pintype "bidirectional"))
    )
    (net (code "127") (name "unconnected-(J4-Pad46)") (class "Default")
      (node (ref "J4") (pin "46") (pinfunction "46_46") (pintype "bidirectional"))
    )
    (net (code "128") (name "unconnected-(OK1-VB-Pad7)") (class "Default")
      (node (ref "OK1") (pin "7") (pinfunction "VB_7") (pintype "passive"))
    )
    (net (code "129") (name "unconnected-(U$1-NC-Pad11)") (class "Default")
      (node (ref "U$1") (pin "11") (pinfunction "NC_11") (pintype "no_connect"))
    )
    (net (code "130") (name "unconnected-(U$2-NC-Pad11)") (class "Default")
      (node (ref "U$2") (pin "11") (pinfunction "NC_11") (pintype "no_connect"))
    )
    (net (code "131") (name "unconnected-(U$3-NC-Pad11)") (class "Default")
      (node (ref "U$3") (pin "11") (pinfunction "NC_11") (pintype "no_connect"))
    )
    (net (code "132") (name "unconnected-(U$4-NC-Pad11)") (class "Default")
      (node (ref "U$4") (pin "11") (pinfunction "NC_11") (pintype "no_connect"))
    )
  )
)
